# body-board.net
KiCad netlist of a schematic drawn in EAGLE
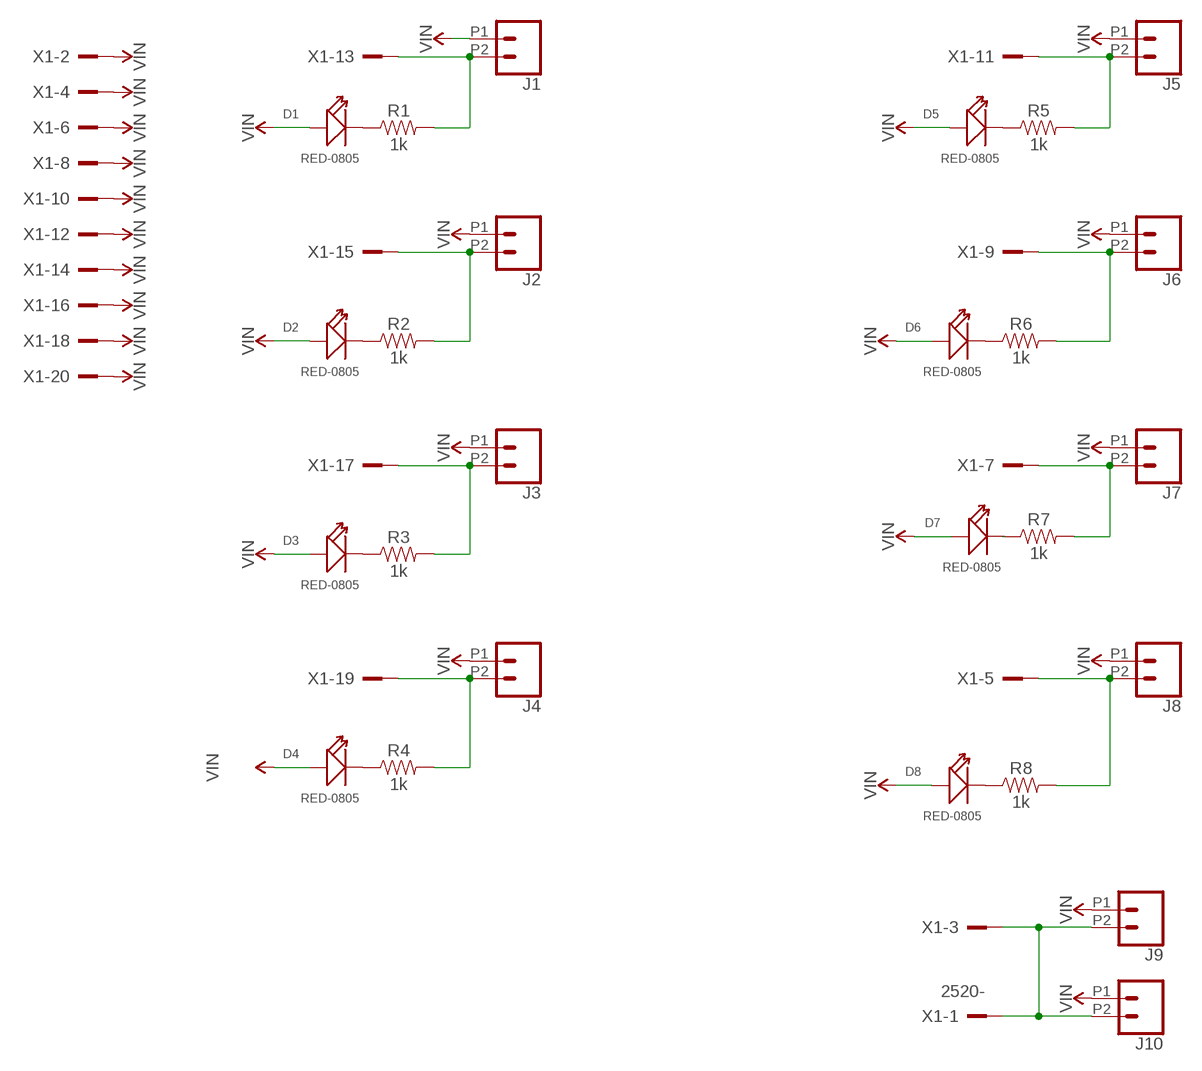
[diagram p0: schematic, sheet 1]

(export (version "E")
  (design (tool "Eeschema 10.0.6"))
  (components
    (comp (ref "D1")
      (value "RED-0805")
      (footprint "eagle-import:LED-0805")
      (fields (field (name "MPN") "17-215SURC/S530-A2/TR8"))
      (libsource (lib "eagle-import") (part "SMD-LED-CLEAR-RED(0805)"))
    )
    (comp (ref "D2")
      (value "RED-0805")
      (footprint "eagle-import:LED-0805")
      (fields (field (name "MPN") "17-215SURC/S530-A2/TR8"))
      (libsource (lib "eagle-import") (part "SMD-LED-CLEAR-RED(0805)"))
    )
    (comp (ref "D3")
      (value "RED-0805")
      (footprint "eagle-import:LED-0805")
      (fields (field (name "MPN") "17-215SURC/S530-A2/TR8"))
      (libsource (lib "eagle-import") (part "SMD-LED-CLEAR-RED(0805)"))
    )
    (comp (ref "D4")
      (value "RED-0805")
      (footprint "eagle-import:LED-0805")
      (fields (field (name "MPN") "17-215SURC/S530-A2/TR8"))
      (libsource (lib "eagle-import") (part "SMD-LED-CLEAR-RED(0805)"))
    )
    (comp (ref "D5")
      (value "RED-0805")
      (footprint "eagle-import:LED-0805")
      (fields (field (name "MPN") "17-215SURC/S530-A2/TR8"))
      (libsource (lib "eagle-import") (part "SMD-LED-CLEAR-RED(0805)"))
    )
    (comp (ref "D6")
      (value "RED-0805")
      (footprint "eagle-import:LED-0805")
      (fields (field (name "MPN") "17-215SURC/S530-A2/TR8"))
      (libsource (lib "eagle-import") (part "SMD-LED-CLEAR-RED(0805)"))
    )
    (comp (ref "D7")
      (value "RED-0805")
      (footprint "eagle-import:LED-0805")
      (fields (field (name "MPN") "17-215SURC/S530-A2/TR8"))
      (libsource (lib "eagle-import") (part "SMD-LED-CLEAR-RED(0805)"))
    )
    (comp (ref "D8")
      (value "RED-0805")
      (footprint "eagle-import:LED-0805")
      (fields (field (name "MPN") "17-215SURC/S530-A2/TR8"))
      (libsource (lib "eagle-import") (part "SMD-LED-CLEAR-RED(0805)"))
    )
    (comp (ref "J1")
      (value "CONN_022.54MM_SCREWTERM")
      (footprint "eagle-import:1X02_2.54_SCREWTERM")
      (libsource (lib "eagle-import") (part "CONN_022.54MM_SCREWTERM"))
    )
    (comp (ref "J2")
      (value "CONN_022.54MM_SCREWTERM")
      (footprint "eagle-import:1X02_2.54_SCREWTERM")
      (libsource (lib "eagle-import") (part "CONN_022.54MM_SCREWTERM"))
    )
    (comp (ref "J3")
      (value "CONN_022.54MM_SCREWTERM")
      (footprint "eagle-import:1X02_2.54_SCREWTERM")
      (libsource (lib "eagle-import") (part "CONN_022.54MM_SCREWTERM"))
    )
    (comp (ref "J4")
      (value "CONN_022.54MM_SCREWTERM")
      (footprint "eagle-import:1X02_2.54_SCREWTERM")
      (libsource (lib "eagle-import") (part "CONN_022.54MM_SCREWTERM"))
    )
    (comp (ref "J5")
      (value "CONN_022.54MM_SCREWTERM")
      (footprint "eagle-import:1X02_2.54_SCREWTERM")
      (libsource (lib "eagle-import") (part "CONN_022.54MM_SCREWTERM"))
    )
    (comp (ref "J6")
      (value "CONN_022.54MM_SCREWTERM")
      (footprint "eagle-import:1X02_2.54_SCREWTERM")
      (libsource (lib "eagle-import") (part "CONN_022.54MM_SCREWTERM"))
    )
    (comp (ref "J7")
      (value "CONN_022.54MM_SCREWTERM")
      (footprint "eagle-import:1X02_2.54_SCREWTERM")
      (libsource (lib "eagle-import") (part "CONN_022.54MM_SCREWTERM"))
    )
    (comp (ref "J8")
      (value "CONN_022.54MM_SCREWTERM")
      (footprint "eagle-import:1X02_2.54_SCREWTERM")
      (libsource (lib "eagle-import") (part "CONN_022.54MM_SCREWTERM"))
    )
    (comp (ref "J9")
      (value "CONN_022.54MM_SCREWTERM")
      (footprint "eagle-import:1X02_2.54_SCREWTERM")
      (libsource (lib "eagle-import") (part "CONN_022.54MM_SCREWTERM"))
    )
    (comp (ref "J10")
      (value "CONN_022.54MM_SCREWTERM")
      (footprint "eagle-import:1X02_2.54_SCREWTERM")
      (libsource (lib "eagle-import") (part "CONN_022.54MM_SCREWTERM"))
    )
    (comp (ref "R1")
      (value "1k")
      (footprint "eagle-import:0603")
      (libsource (lib "eagle-import") (part "1KOHM-0603-1/10W-1%"))
    )
    (comp (ref "R2")
      (value "1k")
      (footprint "eagle-import:0603")
      (libsource (lib "eagle-import") (part "1KOHM-0603-1/10W-1%"))
    )
    (comp (ref "R3")
      (value "1k")
      (footprint "eagle-import:0603")
      (libsource (lib "eagle-import") (part "1KOHM-0603-1/10W-1%"))
    )
    (comp (ref "R4")
      (value "1k")
      (footprint "eagle-import:0603")
      (libsource (lib "eagle-import") (part "1KOHM-0603-1/10W-1%"))
    )
    (comp (ref "R5")
      (value "1k")
      (footprint "eagle-import:0603")
      (libsource (lib "eagle-import") (part "1KOHM-0603-1/10W-1%"))
    )
    (comp (ref "R6")
      (value "1k")
      (footprint "eagle-import:0603")
      (libsource (lib "eagle-import") (part "1KOHM-0603-1/10W-1%"))
    )
    (comp (ref "R7")
      (value "1k")
      (footprint "eagle-import:0603")
      (libsource (lib "eagle-import") (part "1KOHM-0603-1/10W-1%"))
    )
    (comp (ref "R8")
      (value "1k")
      (footprint "eagle-import:0603")
      (libsource (lib "eagle-import") (part "1KOHM-0603-1/10W-1%"))
    )
    (comp (ref "X1")
      (value "2520-")
      (footprint "eagle-import:PAK100_2500-20")
      (libsource (lib "eagle-import") (part "2520-"))
    )
  )
  (nets
    (net (code "1") (name "Net-(D1-Pad-)") (class "Default")
      (node (ref "D1") (pin "-") (pinfunction "-_-") (pintype "passive"))
      (node (ref "R1") (pin "1") (pinfunction "1_1") (pintype "passive"))
    )
    (net (code "2") (name "Net-(D2-Pad-)") (class "Default")
      (node (ref "D2") (pin "-") (pinfunction "-_-") (pintype "passive"))
      (node (ref "R2") (pin "1") (pinfunction "1_1") (pintype "passive"))
    )
    (net (code "3") (name "Net-(D3-Pad-)") (class "Default")
      (node (ref "D3") (pin "-") (pinfunction "-_-") (pintype "passive"))
      (node (ref "R3") (pin "1") (pinfunction "1_1") (pintype "passive"))
    )
    (net (code "4") (name "Net-(D4-Pad-)") (class "Default")
      (node (ref "D4") (pin "-") (pinfunction "-_-") (pintype "passive"))
      (node (ref "R4") (pin "1") (pinfunction "1_1") (pintype "passive"))
    )
    (net (code "5") (name "Net-(D5-Pad-)") (class "Default")
      (node (ref "D5") (pin "-") (pinfunction "-_-") (pintype "passive"))
      (node (ref "R5") (pin "1") (pinfunction "1_1") (pintype "passive"))
    )
    (net (code "6") (name "Net-(D6-Pad-)") (class "Default")
      (node (ref "D6") (pin "-") (pinfunction "-_-") (pintype "passive"))
      (node (ref "R6") (pin "1") (pinfunction "1_1") (pintype "passive"))
    )
    (net (code "7") (name "Net-(D7-Pad-)") (class "Default")
      (node (ref "D7") (pin "-") (pinfunction "-_-") (pintype "passive"))
      (node (ref "R7") (pin "1") (pinfunction "1_1") (pintype "passive"))
    )
    (net (code "8") (name "Net-(D8-Pad-)") (class "Default")
      (node (ref "D8") (pin "-") (pinfunction "-_-") (pintype "passive"))
      (node (ref "R8") (pin "1") (pinfunction "1_1") (pintype "passive"))
    )
    (net (code "9") (name "Net-(J1-2)") (class "Default")
      (node (ref "J1") (pin "P2") (pinfunction "2_P2") (pintype "passive"))
      (node (ref "R1") (pin "2") (pinfunction "2_2") (pintype "passive"))
      (node (ref "X1") (pin "13") (pinfunction "KL_13") (pintype "passive"))
    )
    (net (code "10") (name "Net-(J2-2)") (class "Default")
      (node (ref "J2") (pin "P2") (pinfunction "2_P2") (pintype "passive"))
      (node (ref "R2") (pin "2") (pinfunction "2_2") (pintype "passive"))
      (node (ref "X1") (pin "15") (pinfunction "KL_15") (pintype "passive"))
    )
    (net (code "11") (name "Net-(J3-2)") (class "Default")
      (node (ref "J3") (pin "P2") (pinfunction "2_P2") (pintype "passive"))
      (node (ref "R3") (pin "2") (pinfunction "2_2") (pintype "passive"))
      (node (ref "X1") (pin "17") (pinfunction "KL_17") (pintype "passive"))
    )
    (net (code "12") (name "Net-(J4-2)") (class "Default")
      (node (ref "J4") (pin "P2") (pinfunction "2_P2") (pintype "passive"))
      (node (ref "R4") (pin "2") (pinfunction "2_2") (pintype "passive"))
      (node (ref "X1") (pin "19") (pinfunction "KL_19") (pintype "passive"))
    )
    (net (code "13") (name "Net-(J5-2)") (class "Default")
      (node (ref "J5") (pin "P2") (pinfunction "2_P2") (pintype "passive"))
      (node (ref "R5") (pin "2") (pinfunction "2_2") (pintype "passive"))
      (node (ref "X1") (pin "11") (pinfunction "KL_11") (pintype "passive"))
    )
    (net (code "14") (name "Net-(J6-2)") (class "Default")
      (node (ref "J6") (pin "P2") (pinfunction "2_P2") (pintype "passive"))
      (node (ref "R6") (pin "2") (pinfunction "2_2") (pintype "passive"))
      (node (ref "X1") (pin "9") (pinfunction "KL_9") (pintype "passive"))
    )
    (net (code "15") (name "Net-(J7-2)") (class "Default")
      (node (ref "J7") (pin "P2") (pinfunction "2_P2") (pintype "passive"))
      (node (ref "R7") (pin "2") (pinfunction "2_2") (pintype "passive"))
      (node (ref "X1") (pin "7") (pinfunction "KL_7") (pintype "passive"))
    )
    (net (code "16") (name "Net-(J8-2)") (class "Default")
      (node (ref "J8") (pin "P2") (pinfunction "2_P2") (pintype "passive"))
      (node (ref "R8") (pin "2") (pinfunction "2_2") (pintype "passive"))
      (node (ref "X1") (pin "5") (pinfunction "KL_5") (pintype "passive"))
    )
    (net (code "17") (name "Net-(J10-2)") (class "Default")
      (node (ref "J10") (pin "P2") (pinfunction "2_P2") (pintype "passive"))
      (node (ref "J9") (pin "P2") (pinfunction "2_P2") (pintype "passive"))
      (node (ref "X1") (pin "1") (pinfunction "KL_1") (pintype "passive"))
      (node (ref "X1") (pin "3") (pinfunction "KL_3") (pintype "passive"))
    )
    (net (code "18") (name "VIN") (class "Default")
      (node (ref "D1") (pin "+") (pinfunction "+_+") (pintype "passive"))
      (node (ref "D2") (pin "+") (pinfunction "+_+") (pintype "passive"))
      (node (ref "D3") (pin "+") (pinfunction "+_+") (pintype "passive"))
      (node (ref "D4") (pin "+") (pinfunction "+_+") (pintype "passive"))
      (node (ref "D5") (pin "+") (pinfunction "+_+") (pintype "passive"))
      (node (ref "D6") (pin "+") (pinfunction "+_+") (pintype "passive"))
      (node (ref "D7") (pin "+") (pinfunction "+_+") (pintype "passive"))
      (node (ref "D8") (pin "+") (pinfunction "+_+") (pintype "passive"))
      (node (ref "J1") (pin "P1") (pinfunction "1_P1") (pintype "passive"))
      (node (ref "J10") (pin "P1") (pinfunction "1_P1") (pintype "passive"))
      (node (ref "J2") (pin "P1") (pinfunction "1_P1") (pintype "passive"))
      (node (ref "J3") (pin "P1") (pinfunction "1_P1") (pintype "passive"))
      (node (ref "J4") (pin "P1") (pinfunction "1_P1") (pintype "passive"))
      (node (ref "J5") (pin "P1") (pinfunction "1_P1") (pintype "passive"))
      (node (ref "J6") (pin "P1") (pinfunction "1_P1") (pintype "passive"))
      (node (ref "J7") (pin "P1") (pinfunction "1_P1") (pintype "passive"))
      (node (ref "J8") (pin "P1") (pinfunction "1_P1") (pintype "passive"))
      (node (ref "J9") (pin "P1") (pinfunction "1_P1") (pintype "passive"))
      (node (ref "X1") (pin "10") (pinfunction "KL_10") (pintype "passive"))
      (node (ref "X1") (pin "12") (pinfunction "KL_12") (pintype "passive"))
      (node (ref "X1") (pin "14") (pinfunction "KL_14") (pintype "passive"))
      (node (ref "X1") (pin "16") (pinfunction "KL_16") (pintype "passive"))
      (node (ref "X1") (pin "18") (pinfunction "KL_18") (pintype "passive"))
      (node (ref "X1") (pin "2") (pinfunction "KL_2") (pintype "passive"))
      (node (ref "X1") (pin "20") (pinfunction "KL_20") (pintype "passive"))
      (node (ref "X1") (pin "4") (pinfunction "KL_4") (pintype "passive"))
      (node (ref "X1") (pin "6") (pinfunction "KL_6") (pintype "passive"))
      (node (ref "X1") (pin "8") (pinfunction "KL_8") (pintype "passive"))
    )
  )
)
